# 07_CELLULAR.net
KiCad netlist of a schematic drawn in Altium Designer
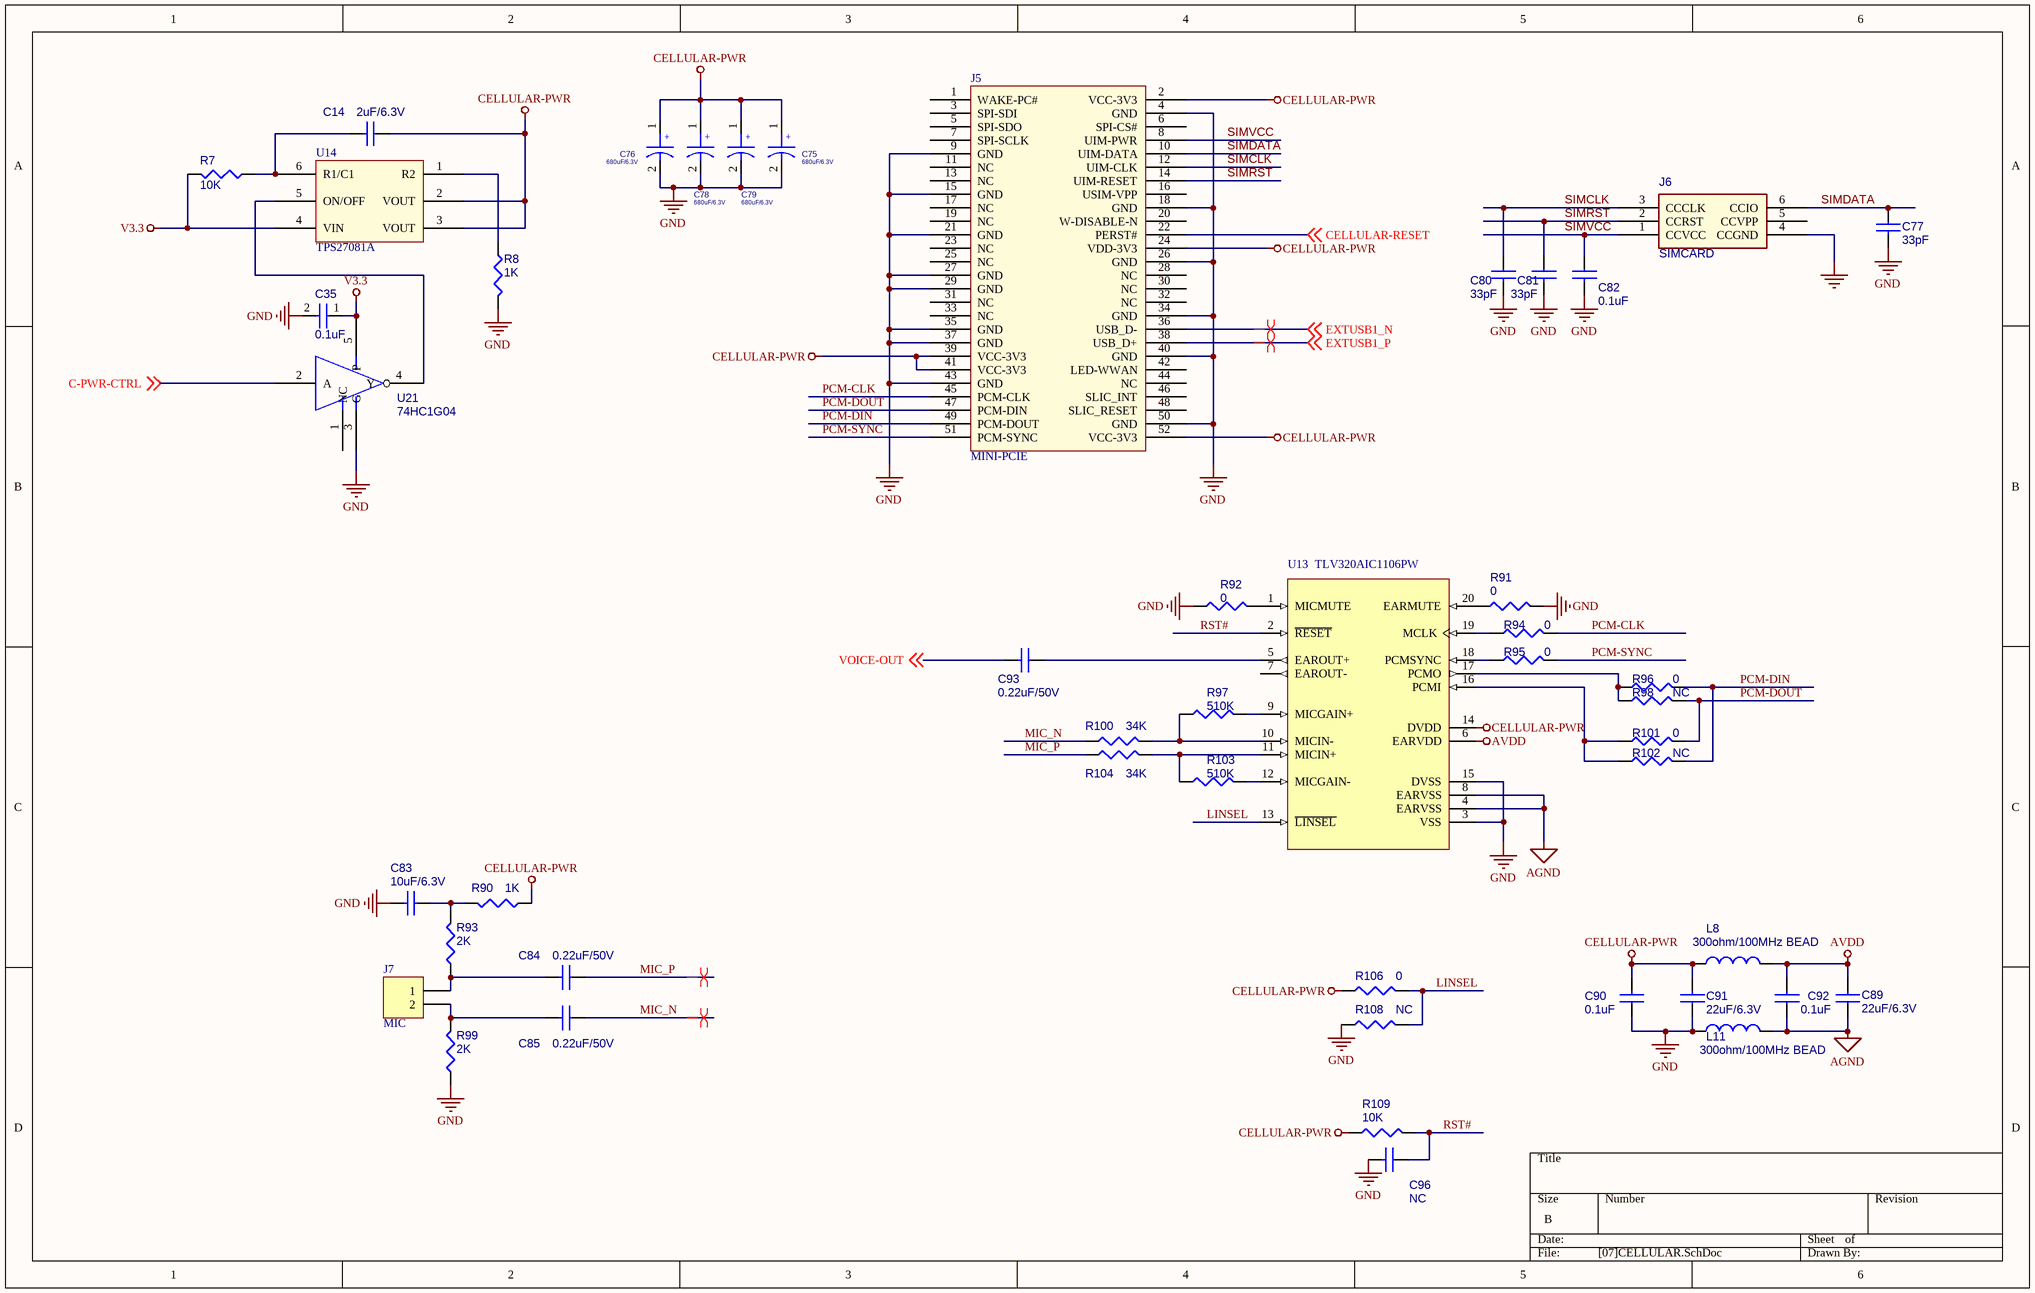
[diagram p0: [07]CELLULAR.SchDoc]

(export (version "E")
  (design (tool "Eeschema 10.0.6"))
  (components
    (comp (ref "C14") (value "2uF/6.3V") (footprint "0603") (libsource (lib "*") (part "P_CAP NP")))
    (comp (ref "C35") (value "0.1uF") (footprint "0603") (libsource (lib "*") (part "CAP NP_Dup2")))
    (comp (ref "C75")
      (value "680uF/6.3V")
      (footprint "7343")
      (description "CAP;10U  ,TT,20V ,20%,6032,SMT")
      (libsource (lib "*") (part "10U-6032-20V"))
    )
    (comp (ref "C76")
      (value "680uF/6.3V")
      (footprint "7343")
      (description "CAP;10U  ,TT,20V ,20%,6032,SMT")
      (libsource (lib "*") (part "10U-6032-20V"))
    )
    (comp (ref "C77") (value "33pF") (libsource (lib "*") (part "P_CAP NP")))
    (comp (ref "C78")
      (value "680uF/6.3V")
      (footprint "7343")
      (description "CAP;10U  ,TT,20V ,20%,6032,SMT")
      (libsource (lib "*") (part "10U-6032-20V"))
    )
    (comp (ref "C79")
      (value "680uF/6.3V")
      (footprint "7343")
      (description "CAP;10U  ,TT,20V ,20%,6032,SMT")
      (libsource (lib "*") (part "10U-6032-20V"))
    )
    (comp (ref "C80") (value "33pF") (libsource (lib "*") (part "P_CAP NP")))
    (comp (ref "C81") (value "33pF") (libsource (lib "*") (part "P_CAP NP")))
    (comp (ref "C82") (value "0.1uF") (libsource (lib "*") (part "P_CAP NP")))
    (comp (ref "C83") (value "10uF/6.3V") (footprint "0805") (libsource (lib "*") (part "P_CAP NP")))
    (comp (ref "C84") (value "0.22uF/50V") (footprint "0603") (libsource (lib "*") (part "P_CAP NP")))
    (comp (ref "C85") (value "0.22uF/50V") (footprint "0603") (libsource (lib "*") (part "P_CAP NP")))
    (comp (ref "C89") (value "22uF/6.3V") (libsource (lib "*") (part "P_CAP NP")))
    (comp (ref "C90") (value "0.1uF") (libsource (lib "*") (part "P_CAP NP")))
    (comp (ref "C91") (value "22uF/6.3V") (libsource (lib "*") (part "P_CAP NP")))
    (comp (ref "C92") (value "0.1uF") (libsource (lib "*") (part "P_CAP NP")))
    (comp (ref "C93") (value "0.22uF/50V") (footprint "0603") (libsource (lib "*") (part "P_CAP NP")))
    (comp (ref "C96") (value "NC") (footprint "0603") (libsource (lib "*") (part "P_CAP NP")))
    (comp (ref "J5")
      (value "MINI-PCIE")
      (footprint "MINI-PCIE")
      (libsource (lib "Schlib") (part "MINI-PCIE"))
    )
    (comp (ref "J6") (value "SIMCARD") (footprint "SIMLOCK2") (libsource (lib "*") (part "SIMCARD")))
    (comp (ref "J7")
      (value "MIC")
      (footprint "CON-2PIN")
      (description "Header, 2-Pin")
      (fields (field (name "PUBLISHER") "Altium Limited"))
      (libsource (lib "Miscellaneous Connectors") (part "Header 2"))
    )
    (comp (ref "L8") (value "300ohm/100MHz BEAD") (libsource (lib "*") (part "INDUCTOR_4")))
    (comp (ref "L11") (value "300ohm/100MHz BEAD") (libsource (lib "*") (part "INDUCTOR_4")))
    (comp (ref "R7") (value "10K") (footprint "0603") (libsource (lib "*") (part "P_R")))
    (comp (ref "R8") (value "1K") (footprint "0603") (libsource (lib "*") (part "P_R")))
    (comp (ref "R90") (value "1K") (footprint "0603") (libsource (lib "*") (part "P_R")))
    (comp (ref "R91") (value "0") (footprint "0603") (libsource (lib "*") (part "P_R")))
    (comp (ref "R92") (value "0") (footprint "0603") (libsource (lib "*") (part "P_R")))
    (comp (ref "R93") (value "2K") (footprint "0603") (libsource (lib "*") (part "P_R")))
    (comp (ref "R94") (value "0") (footprint "0603") (libsource (lib "*") (part "P_R")))
    (comp (ref "R95") (value "0") (footprint "0603") (libsource (lib "*") (part "P_R")))
    (comp (ref "R96") (value "0") (footprint "0603") (libsource (lib "*") (part "P_R")))
    (comp (ref "R97") (value "510K") (footprint "0603") (libsource (lib "*") (part "P_R")))
    (comp (ref "R98") (value "NC") (footprint "0603") (libsource (lib "*") (part "P_R")))
    (comp (ref "R99") (value "2K") (footprint "0603") (libsource (lib "*") (part "P_R")))
    (comp (ref "R100") (value "34K") (footprint "0603") (libsource (lib "*") (part "P_R")))
    (comp (ref "R101") (value "0") (footprint "0603") (libsource (lib "*") (part "P_R")))
    (comp (ref "R102") (value "NC") (footprint "0603") (libsource (lib "*") (part "P_R")))
    (comp (ref "R103") (value "510K") (footprint "0603") (libsource (lib "*") (part "P_R")))
    (comp (ref "R104") (value "34K") (footprint "0603") (libsource (lib "*") (part "P_R")))
    (comp (ref "R106") (value "0") (footprint "0603") (libsource (lib "*") (part "P_R")))
    (comp (ref "R108") (value "NC") (footprint "0603") (libsource (lib "*") (part "P_R")))
    (comp (ref "R109") (value "10K") (footprint "0603") (libsource (lib "*") (part "P_R")))
    (comp (ref "U13")
      (value "TLV320AIC1106PW")
      (footprint "PW020")
      (description "PCM CODEC With Microphone Amps & Speaker Driver, 20-Pin TSSOP")
      (fields (field (name "PUBLISHER") "Altium Limited"))
      (libsource (lib "TI Converter CODEC Voice-Band") (part "TLV320AIC1106PWG4"))
    )
    (comp (ref "U14") (value "TPS27081A") (footprint "SOT23-6") (libsource (lib "Schlib") (part "TPS27081A")))
    (comp (ref "U21") (value "74HC1G04") (libsource (lib "*") (part "74LVC1G04GW_SOT353-5")))
  )
  (nets
    (net (code "1") (name "/LINSEL") (class "Default")
      (node (ref "R106") (pin "1") (pinfunction "1_1") (pintype "passive"))
      (node (ref "R108") (pin "1") (pinfunction "1_1") (pintype "passive"))
      (node (ref "U13") (pin "13") (pinfunction "~{LINSEL}_13") (pintype "input"))
    )
    (net (code "2") (name "/MIC_N") (class "Default")
      (node (ref "C85") (pin "1") (pinfunction "1_1") (pintype "passive"))
      (node (ref "R100") (pin "2") (pinfunction "2_2") (pintype "passive"))
    )
    (net (code "3") (name "/MIC_P") (class "Default")
      (node (ref "C84") (pin "1") (pinfunction "1_1") (pintype "passive"))
      (node (ref "R104") (pin "2") (pinfunction "2_2") (pintype "passive"))
    )
    (net (code "4") (name "/PCM-CLK") (class "Default")
      (node (ref "J5") (pin "45") (pinfunction "PCM-CLK_45") (pintype "passive"))
      (node (ref "R94") (pin "1") (pinfunction "1_1") (pintype "passive"))
    )
    (net (code "5") (name "/PCM-DIN") (class "Default")
      (node (ref "J5") (pin "49") (pinfunction "PCM-DOUT_49") (pintype "passive"))
      (node (ref "R102") (pin "1") (pinfunction "1_1") (pintype "passive"))
      (node (ref "R96") (pin "1") (pinfunction "1_1") (pintype "passive"))
    )
    (net (code "6") (name "/PCM-DOUT") (class "Default")
      (node (ref "J5") (pin "47") (pinfunction "PCM-DIN_47") (pintype "passive"))
      (node (ref "R101") (pin "1") (pinfunction "1_1") (pintype "passive"))
      (node (ref "R98") (pin "1") (pinfunction "1_1") (pintype "passive"))
    )
    (net (code "7") (name "/PCM-SYNC") (class "Default")
      (node (ref "J5") (pin "51") (pinfunction "PCM-SYNC_51") (pintype "passive"))
      (node (ref "R95") (pin "1") (pinfunction "1_1") (pintype "passive"))
    )
    (net (code "8") (name "/RST#") (class "Default")
      (node (ref "C96") (pin "1") (pinfunction "1_1") (pintype "passive"))
      (node (ref "R109") (pin "1") (pinfunction "1_1") (pintype "passive"))
      (node (ref "U13") (pin "2") (pinfunction "~{RESET}_2") (pintype "input"))
    )
    (net (code "9") (name "/SIMCLK") (class "Default")
      (node (ref "C80") (pin "1") (pinfunction "1_1") (pintype "passive"))
      (node (ref "J5") (pin "12") (pinfunction "UIM-CLK_12") (pintype "passive"))
      (node (ref "J6") (pin "3") (pinfunction "CCCLK_3") (pintype "passive"))
    )
    (net (code "10") (name "/SIMDATA") (class "Default")
      (node (ref "C77") (pin "1") (pinfunction "1_1") (pintype "passive"))
      (node (ref "J5") (pin "10") (pinfunction "UIM-DATA_10") (pintype "passive"))
      (node (ref "J6") (pin "6") (pinfunction "CCIO_6") (pintype "passive"))
    )
    (net (code "11") (name "/SIMRST") (class "Default")
      (node (ref "C81") (pin "1") (pinfunction "1_1") (pintype "passive"))
      (node (ref "J5") (pin "14") (pinfunction "UIM-RESET_14") (pintype "passive"))
      (node (ref "J6") (pin "2") (pinfunction "CCRST_2") (pintype "passive"))
    )
    (net (code "12") (name "/SIMVCC") (class "Default")
      (node (ref "C82") (pin "1") (pinfunction "1_1") (pintype "passive"))
      (node (ref "J5") (pin "8") (pinfunction "UIM-PWR_8") (pintype "passive"))
      (node (ref "J6") (pin "1") (pinfunction "CCVCC_1") (pintype "passive"))
    )
    (net (code "13") (name "AGND") (class "Default")
      (node (ref "C89") (pin "1") (pinfunction "1_1") (pintype "passive"))
      (node (ref "C92") (pin "1") (pinfunction "1_1") (pintype "passive"))
      (node (ref "L11") (pin "1") (pinfunction "1_1") (pintype "passive"))
      (node (ref "U13") (pin "4") (pinfunction "EARVSS_4") (pintype "power_in"))
      (node (ref "U13") (pin "8") (pinfunction "EARVSS_8") (pintype "power_in"))
    )
    (net (code "14") (name "AVDD") (class "Default")
      (node (ref "C89") (pin "2") (pinfunction "2_2") (pintype "passive"))
      (node (ref "C92") (pin "2") (pinfunction "2_2") (pintype "passive"))
      (node (ref "L8") (pin "1") (pinfunction "1_1") (pintype "passive"))
      (node (ref "U13") (pin "6") (pinfunction "EARVDD_6") (pintype "power_in"))
    )
    (net (code "15") (name "C-PWR-CTRL") (class "Default")
      (node (ref "U21") (pin "2") (pinfunction "A_2") (pintype "passive"))
    )
    (net (code "16") (name "CELLULAR-PWR") (class "Default")
      (node (ref "C14") (pin "1") (pinfunction "1_1") (pintype "passive"))
      (node (ref "C75") (pin "1") (pinfunction "1_1") (pintype "passive"))
      (node (ref "C76") (pin "1") (pinfunction "1_1") (pintype "passive"))
      (node (ref "C78") (pin "1") (pinfunction "1_1") (pintype "passive"))
      (node (ref "C79") (pin "1") (pinfunction "1_1") (pintype "passive"))
      (node (ref "C90") (pin "2") (pinfunction "2_2") (pintype "passive"))
      (node (ref "C91") (pin "2") (pinfunction "2_2") (pintype "passive"))
      (node (ref "J5") (pin "2") (pinfunction "VCC-3V3_2") (pintype "passive"))
      (node (ref "J5") (pin "24") (pinfunction "VDD-3V3_24") (pintype "passive"))
      (node (ref "J5") (pin "39") (pinfunction "VCC-3V3_39") (pintype "passive"))
      (node (ref "J5") (pin "41") (pinfunction "VCC-3V3_41") (pintype "passive"))
      (node (ref "J5") (pin "52") (pinfunction "VCC-3V3_52") (pintype "passive"))
      (node (ref "L8") (pin "2") (pinfunction "2_2") (pintype "passive"))
      (node (ref "R106") (pin "2") (pinfunction "2_2") (pintype "passive"))
      (node (ref "R109") (pin "2") (pinfunction "2_2") (pintype "passive"))
      (node (ref "R90") (pin "2") (pinfunction "2_2") (pintype "passive"))
      (node (ref "U13") (pin "14") (pinfunction "DVDD_14") (pintype "power_in"))
      (node (ref "U14") (pin "2") (pinfunction "VOUT_2") (pintype "passive"))
      (node (ref "U14") (pin "3") (pinfunction "VOUT_3") (pintype "passive"))
    )
    (net (code "17") (name "CELLULAR-RESET") (class "Default")
      (node (ref "J5") (pin "22") (pinfunction "PERST#_22") (pintype "passive"))
    )
    (net (code "18") (name "EXTUSB1_N") (class "Default")
      (node (ref "J5") (pin "36") (pinfunction "USB_D-_36") (pintype "passive"))
    )
    (net (code "19") (name "EXTUSB1_P") (class "Default")
      (node (ref "J5") (pin "38") (pinfunction "USB_D+_38") (pintype "passive"))
    )
    (net (code "20") (name "GND") (class "Default")
      (node (ref "C35") (pin "2") (pinfunction "2_2") (pintype "passive"))
      (node (ref "C75") (pin "2") (pinfunction "2_2") (pintype "passive"))
      (node (ref "C76") (pin "2") (pinfunction "2_2") (pintype "passive"))
      (node (ref "C77") (pin "2") (pinfunction "2_2") (pintype "passive"))
      (node (ref "C78") (pin "2") (pinfunction "2_2") (pintype "passive"))
      (node (ref "C79") (pin "2") (pinfunction "2_2") (pintype "passive"))
      (node (ref "C80") (pin "2") (pinfunction "2_2") (pintype "passive"))
      (node (ref "C81") (pin "2") (pinfunction "2_2") (pintype "passive"))
      (node (ref "C82") (pin "2") (pinfunction "2_2") (pintype "passive"))
      (node (ref "C83") (pin "2") (pinfunction "2_2") (pintype "passive"))
      (node (ref "C90") (pin "1") (pinfunction "1_1") (pintype "passive"))
      (node (ref "C91") (pin "1") (pinfunction "1_1") (pintype "passive"))
      (node (ref "C96") (pin "2") (pinfunction "2_2") (pintype "passive"))
      (node (ref "J5") (pin "15") (pinfunction "GND_15") (pintype "passive"))
      (node (ref "J5") (pin "18") (pinfunction "GND_18") (pintype "passive"))
      (node (ref "J5") (pin "21") (pinfunction "GND_21") (pintype "passive"))
      (node (ref "J5") (pin "26") (pinfunction "GND_26") (pintype "passive"))
      (node (ref "J5") (pin "27") (pinfunction "GND_27") (pintype "passive"))
      (node (ref "J5") (pin "29") (pinfunction "GND_29") (pintype "passive"))
      (node (ref "J5") (pin "34") (pinfunction "GND_34") (pintype "passive"))
      (node (ref "J5") (pin "35") (pinfunction "GND_35") (pintype "passive"))
      (node (ref "J5") (pin "37") (pinfunction "GND_37") (pintype "passive"))
      (node (ref "J5") (pin "4") (pinfunction "GND_4") (pintype "passive"))
      (node (ref "J5") (pin "40") (pinfunction "GND_40") (pintype "passive"))
      (node (ref "J5") (pin "43") (pinfunction "GND_43") (pintype "passive"))
      (node (ref "J5") (pin "50") (pinfunction "GND_50") (pintype "passive"))
      (node (ref "J5") (pin "9") (pinfunction "GND_9") (pintype "passive"))
      (node (ref "J6") (pin "4") (pinfunction "CCGND_4") (pintype "passive"))
      (node (ref "L11") (pin "2") (pinfunction "2_2") (pintype "passive"))
      (node (ref "R108") (pin "2") (pinfunction "2_2") (pintype "passive"))
      (node (ref "R8") (pin "1") (pinfunction "1_1") (pintype "passive"))
      (node (ref "R91") (pin "1") (pinfunction "1_1") (pintype "passive"))
      (node (ref "R92") (pin "2") (pinfunction "2_2") (pintype "passive"))
      (node (ref "R99") (pin "2") (pinfunction "2_2") (pintype "passive"))
      (node (ref "U13") (pin "15") (pinfunction "DVSS_15") (pintype "power_in"))
      (node (ref "U13") (pin "3") (pinfunction "VSS_3") (pintype "power_in"))
      (node (ref "U21") (pin "3") (pinfunction "G_3") (pintype "passive"))
    )
    (net (code "21") (name "Net-(C83-Pad1)") (class "Default")
      (node (ref "C83") (pin "1") (pinfunction "1_1") (pintype "passive"))
      (node (ref "R90") (pin "1") (pinfunction "1_1") (pintype "passive"))
      (node (ref "R93") (pin "1") (pinfunction "1_1") (pintype "passive"))
    )
    (net (code "22") (name "Net-(C84-Pad2)") (class "Default")
      (node (ref "C84") (pin "2") (pinfunction "2_2") (pintype "passive"))
      (node (ref "J7") (pin "1") (pinfunction "1_1") (pintype "passive"))
      (node (ref "R93") (pin "2") (pinfunction "2_2") (pintype "passive"))
    )
    (net (code "23") (name "Net-(C85-Pad2)") (class "Default")
      (node (ref "C85") (pin "2") (pinfunction "2_2") (pintype "passive"))
      (node (ref "J7") (pin "2") (pinfunction "2_2") (pintype "passive"))
      (node (ref "R99") (pin "1") (pinfunction "1_1") (pintype "passive"))
    )
    (net (code "24") (name "Net-(U13-EARMUTE)") (class "Default")
      (node (ref "R91") (pin "2") (pinfunction "2_2") (pintype "passive"))
      (node (ref "U13") (pin "20") (pinfunction "EARMUTE_20") (pintype "input"))
    )
    (net (code "25") (name "Net-(U13-EAROUT+)") (class "Default")
      (node (ref "C93") (pin "1") (pinfunction "1_1") (pintype "passive"))
      (node (ref "U13") (pin "5") (pinfunction "EAROUT+_5") (pintype "output"))
    )
    (net (code "26") (name "Net-(U13-MCLK)") (class "Default")
      (node (ref "R94") (pin "2") (pinfunction "2_2") (pintype "passive"))
      (node (ref "U13") (pin "19") (pinfunction "MCLK_19") (pintype "input"))
    )
    (net (code "27") (name "Net-(U13-MICGAIN+)") (class "Default")
      (node (ref "R97") (pin "1") (pinfunction "1_1") (pintype "passive"))
      (node (ref "U13") (pin "9") (pinfunction "MICGAIN+_9") (pintype "input"))
    )
    (net (code "28") (name "Net-(U13-MICGAIN-)") (class "Default")
      (node (ref "R103") (pin "1") (pinfunction "1_1") (pintype "passive"))
      (node (ref "U13") (pin "12") (pinfunction "MICGAIN-_12") (pintype "input"))
    )
    (net (code "29") (name "Net-(U13-MICIN+)") (class "Default")
      (node (ref "R103") (pin "2") (pinfunction "2_2") (pintype "passive"))
      (node (ref "R104") (pin "1") (pinfunction "1_1") (pintype "passive"))
      (node (ref "U13") (pin "11") (pinfunction "MICIN+_11") (pintype "input"))
    )
    (net (code "30") (name "Net-(U13-MICIN-)") (class "Default")
      (node (ref "R100") (pin "1") (pinfunction "1_1") (pintype "passive"))
      (node (ref "R97") (pin "2") (pinfunction "2_2") (pintype "passive"))
      (node (ref "U13") (pin "10") (pinfunction "MICIN-_10") (pintype "input"))
    )
    (net (code "31") (name "Net-(U13-MICMUTE)") (class "Default")
      (node (ref "R92") (pin "1") (pinfunction "1_1") (pintype "passive"))
      (node (ref "U13") (pin "1") (pinfunction "MICMUTE_1") (pintype "input"))
    )
    (net (code "32") (name "Net-(U13-PCMI)") (class "Default")
      (node (ref "R101") (pin "2") (pinfunction "2_2") (pintype "passive"))
      (node (ref "R102") (pin "2") (pinfunction "2_2") (pintype "passive"))
      (node (ref "U13") (pin "16") (pinfunction "PCMI_16") (pintype "input"))
    )
    (net (code "33") (name "Net-(U13-PCMO)") (class "Default")
      (node (ref "R96") (pin "2") (pinfunction "2_2") (pintype "passive"))
      (node (ref "R98") (pin "2") (pinfunction "2_2") (pintype "passive"))
      (node (ref "U13") (pin "17") (pinfunction "PCMO_17") (pintype "output"))
    )
    (net (code "34") (name "Net-(U13-PCMSYNC)") (class "Default")
      (node (ref "R95") (pin "2") (pinfunction "2_2") (pintype "passive"))
      (node (ref "U13") (pin "18") (pinfunction "PCMSYNC_18") (pintype "input"))
    )
    (net (code "35") (name "Net-(U14-ON{slash}OFF)") (class "Default")
      (node (ref "U14") (pin "5") (pinfunction "ON/OFF_5") (pintype "passive"))
      (node (ref "U21") (pin "4") (pinfunction "Y_4") (pintype "passive"))
    )
    (net (code "36") (name "Net-(U14-R1{slash}C1)") (class "Default")
      (node (ref "C14") (pin "2") (pinfunction "2_2") (pintype "passive"))
      (node (ref "R7") (pin "2") (pinfunction "2_2") (pintype "passive"))
      (node (ref "U14") (pin "6") (pinfunction "R1/C1_6") (pintype "passive"))
    )
    (net (code "37") (name "Net-(U14-R2)") (class "Default")
      (node (ref "R8") (pin "2") (pinfunction "2_2") (pintype "passive"))
      (node (ref "U14") (pin "1") (pinfunction "R2_1") (pintype "passive"))
    )
    (net (code "38") (name "V3.3") (class "Default")
      (node (ref "C35") (pin "1") (pinfunction "1_1") (pintype "passive"))
      (node (ref "R7") (pin "1") (pinfunction "1_1") (pintype "passive"))
      (node (ref "U14") (pin "4") (pinfunction "VIN_4") (pintype "passive"))
      (node (ref "U21") (pin "5") (pinfunction "P_5") (pintype "passive"))
    )
    (net (code "39") (name "VOICE-OUT") (class "Default")
      (node (ref "C93") (pin "2") (pinfunction "2_2") (pintype "passive"))
    )
    (net (code "40") (name "unconnected-(J5-LED-WWAN-Pad42)") (class "Default")
      (node (ref "J5") (pin "42") (pinfunction "LED-WWAN_42") (pintype "passive"))
    )
    (net (code "41") (name "unconnected-(J5-NC-Pad11)") (class "Default")
      (node (ref "J5") (pin "11") (pinfunction "NC_11") (pintype "passive"))
    )
    (net (code "42") (name "unconnected-(J5-NC-Pad13)") (class "Default")
      (node (ref "J5") (pin "13") (pinfunction "NC_13") (pintype "passive"))
    )
    (net (code "43") (name "unconnected-(J5-NC-Pad17)") (class "Default")
      (node (ref "J5") (pin "17") (pinfunction "NC_17") (pintype "passive"))
    )
    (net (code "44") (name "unconnected-(J5-NC-Pad19)") (class "Default")
      (node (ref "J5") (pin "19") (pinfunction "NC_19") (pintype "passive"))
    )
    (net (code "45") (name "unconnected-(J5-NC-Pad23)") (class "Default")
      (node (ref "J5") (pin "23") (pinfunction "NC_23") (pintype "passive"))
    )
    (net (code "46") (name "unconnected-(J5-NC-Pad25)") (class "Default")
      (node (ref "J5") (pin "25") (pinfunction "NC_25") (pintype "passive"))
    )
    (net (code "47") (name "unconnected-(J5-NC-Pad28)") (class "Default")
      (node (ref "J5") (pin "28") (pinfunction "NC_28") (pintype "passive"))
    )
    (net (code "48") (name "unconnected-(J5-NC-Pad30)") (class "Default")
      (node (ref "J5") (pin "30") (pinfunction "NC_30") (pintype "passive"))
    )
    (net (code "49") (name "unconnected-(J5-NC-Pad31)") (class "Default")
      (node (ref "J5") (pin "31") (pinfunction "NC_31") (pintype "passive"))
    )
    (net (code "50") (name "unconnected-(J5-NC-Pad32)") (class "Default")
      (node (ref "J5") (pin "32") (pinfunction "NC_32") (pintype "passive"))
    )
    (net (code "51") (name "unconnected-(J5-NC-Pad33)") (class "Default")
      (node (ref "J5") (pin "33") (pinfunction "NC_33") (pintype "passive"))
    )
    (net (code "52") (name "unconnected-(J5-NC-Pad44)") (class "Default")
      (node (ref "J5") (pin "44") (pinfunction "NC_44") (pintype "passive"))
    )
    (net (code "53") (name "unconnected-(J5-SLIC_INT-Pad46)") (class "Default")
      (node (ref "J5") (pin "46") (pinfunction "SLIC_INT_46") (pintype "passive"))
    )
    (net (code "54") (name "unconnected-(J5-SLIC_RESET-Pad48)") (class "Default")
      (node (ref "J5") (pin "48") (pinfunction "SLIC_RESET_48") (pintype "passive"))
    )
    (net (code "55") (name "unconnected-(J5-SPI-CS#-Pad6)") (class "Default")
      (node (ref "J5") (pin "6") (pinfunction "SPI-CS#_6") (pintype "passive"))
    )
    (net (code "56") (name "unconnected-(J5-SPI-SCLK-Pad7)") (class "Default")
      (node (ref "J5") (pin "7") (pinfunction "SPI-SCLK_7") (pintype "passive"))
    )
    (net (code "57") (name "unconnected-(J5-SPI-SDI-Pad3)") (class "Default")
      (node (ref "J5") (pin "3") (pinfunction "SPI-SDI_3") (pintype "passive"))
    )
    (net (code "58") (name "unconnected-(J5-SPI-SDO-Pad5)") (class "Default")
      (node (ref "J5") (pin "5") (pinfunction "SPI-SDO_5") (pintype "passive"))
    )
    (net (code "59") (name "unconnected-(J5-USIM-VPP-Pad16)") (class "Default")
      (node (ref "J5") (pin "16") (pinfunction "USIM-VPP_16") (pintype "passive"))
    )
    (net (code "60") (name "unconnected-(J5-W-DISABLE-N-Pad20)") (class "Default")
      (node (ref "J5") (pin "20") (pinfunction "W-DISABLE-N_20") (pintype "passive"))
    )
    (net (code "61") (name "unconnected-(J5-WAKE-PC#-Pad1)") (class "Default")
      (node (ref "J5") (pin "1") (pinfunction "WAKE-PC#_1") (pintype "passive"))
    )
    (net (code "62") (name "unconnected-(J6-CCVPP-Pad5)") (class "Default")
      (node (ref "J6") (pin "5") (pinfunction "CCVPP_5") (pintype "passive"))
    )
    (net (code "63") (name "unconnected-(U13-EAROUT--Pad7)") (class "Default")
      (node (ref "U13") (pin "7") (pinfunction "EAROUT-_7") (pintype "output"))
    )
    (net (code "64") (name "unconnected-(U21-NC-Pad1)") (class "Default")
      (node (ref "U21") (pin "1") (pinfunction "NC_1") (pintype "passive"))
    )
  )
)
